# usb_serial.net
KiCad netlist of a schematic drawn in Altium Designer
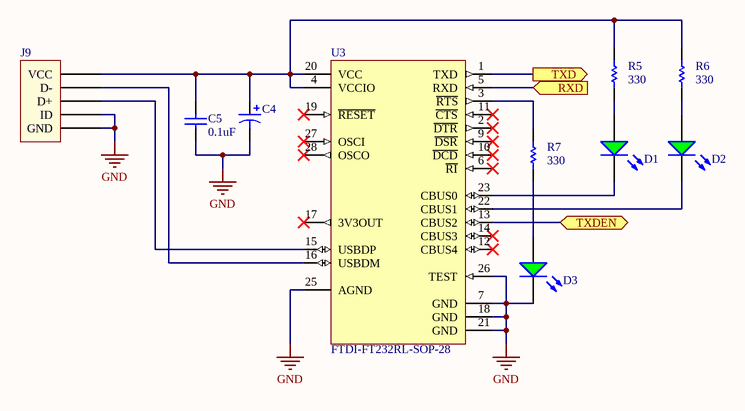
[diagram p0: usb_serial.SchDoc]

(export (version "E")
  (design (tool "Eeschema 10.0.6"))
  (components
    (comp (ref "C4")
      (value "Cap Pol2")
      (footprint "PCB-egxxoj2f8mz0uec15l92-1")
      (fields (field (name "MANUFACTURER PART NUMBER") "F981C105MMA"))
      (libsource (lib "CommunityVault") (part "CMP-7994653-3"))
    )
    (comp (ref "C5")
      (value "0.1uF")
      (footprint "CAPC1608X90X35NL20T15")
      (description "CAP CER 0.1UF 50V 10% X7R 0603")
      (libsource (lib "CommunityVault") (part "CMP-120344-2"))
    )
    (comp (ref "D1")
      (value "SYM-ec4c254b98bc338b-2")
      (footprint "PCB-9uwk2xd6chnjs8ehct7l-1")
      (description "Led; 0603 Smt Led, Green, Alingap, Water Clear Lens, 140 Deg Viewing Angle")
      (libsource (lib "CommunityVault") (part "CMP-ec4c254b98bc338b-4"))
    )
    (comp (ref "D2")
      (value "SYM-ec4c254b98bc338b-2")
      (footprint "PCB-9uwk2xd6chnjs8ehct7l-1")
      (description "Led; 0603 Smt Led, Green, Alingap, Water Clear Lens, 140 Deg Viewing Angle")
      (libsource (lib "CommunityVault") (part "CMP-ec4c254b98bc338b-4"))
    )
    (comp (ref "D3")
      (value "SYM-ec4c254b98bc338b-2")
      (footprint "PCB-9uwk2xd6chnjs8ehct7l-1")
      (description "Led; 0603 Smt Led, Green, Alingap, Water Clear Lens, 140 Deg Viewing Angle")
      (libsource (lib "CommunityVault") (part "CMP-ec4c254b98bc338b-4"))
    )
    (comp (ref "J9")
      (value "Samtec SPM-05-S-B-RA-PF")
      (footprint "PCB-zq8ywneimcsz1qyvw1ex-1")
      (description "Conn USB M 5 POS Solder RA Thru-Hole 5 Terminal 1 Port")
      (fields (field (name "MANUFACTURER PART NUMBER") "SPM-05-S-B-RA-PF"))
      (libsource (lib "CommunityVault") (part "CMP-d3c01be030ed0c07-2"))
    )
    (comp (ref "R5")
      (value "330")
      (footprint "PCB-1852941-1")
      (description "RESISTOR, RC21 0603 330R")
      (fields (field (name "MANUFACTURER PART NUMBER") "RC0603JR-07330RL"))
      (libsource (lib "CommunityVault") (part "CMP-1852941-3"))
    )
    (comp (ref "R6")
      (value "330")
      (footprint "PCB-1852941-1")
      (description "RESISTOR, RC21 0603 330R")
      (fields (field (name "MANUFACTURER PART NUMBER") "RC0603JR-07330RL"))
      (libsource (lib "CommunityVault") (part "CMP-1852941-3"))
    )
    (comp (ref "R7")
      (value "330")
      (footprint "PCB-1852941-1")
      (description "RESISTOR, RC21 0603 330R")
      (fields (field (name "MANUFACTURER PART NUMBER") "RC0603JR-07330RL"))
      (libsource (lib "CommunityVault") (part "CMP-1852941-3"))
    )
    (comp (ref "U3")
      (value "FTDI-FT232RL-SOP-28")
      (footprint "SOP65P780X200-28N")
      (description "SMD IC Interface; USB to UART; Speed 300b-3Mbaud; VCC 1.8V-5.25V")
      (fields (field (name "MANUFACTURER PART NUMBER") "FT232RL"))
      (libsource (lib "CommunityVault") (part "CMP-1159378-16"))
    )
  )
  (nets
    (net (code "1") (name "/RXD") (class "Default")
      (node (ref "U3") (pin "5") (pinfunction "RXD_5") (pintype "input"))
    )
    (net (code "2") (name "/TXD") (class "Default")
      (node (ref "U3") (pin "1") (pinfunction "TXD_1") (pintype "output"))
    )
    (net (code "3") (name "/TXDEN") (class "Default")
      (node (ref "U3") (pin "13") (pinfunction "CBUS2_13") (pintype "bidirectional"))
    )
    (net (code "4") (name "GND") (class "Default")
      (node (ref "C4") (pin "2") (pinfunction "2_2") (pintype "passive"))
      (node (ref "C5") (pin "1") (pinfunction "1_1") (pintype "passive"))
      (node (ref "D3") (pin "C") (pinfunction "C_C") (pintype "passive"))
      (node (ref "J9") (pin "4") (pinfunction "ID_4") (pintype "passive"))
      (node (ref "J9") (pin "5") (pinfunction "GND_5") (pintype "passive"))
      (node (ref "U3") (pin "18") (pinfunction "GND_18") (pintype "power_in"))
      (node (ref "U3") (pin "21") (pinfunction "GND_21") (pintype "power_in"))
      (node (ref "U3") (pin "25") (pinfunction "AGND_25") (pintype "power_in"))
      (node (ref "U3") (pin "26") (pinfunction "TEST_26") (pintype "input"))
      (node (ref "U3") (pin "7") (pinfunction "GND_7") (pintype "power_in"))
    )
    (net (code "5") (name "Net-(D1-PadA)") (class "Default")
      (node (ref "D1") (pin "A") (pinfunction "A_A") (pintype "passive"))
      (node (ref "R5") (pin "1") (pinfunction "1_1") (pintype "passive"))
    )
    (net (code "6") (name "Net-(D2-PadA)") (class "Default")
      (node (ref "D2") (pin "A") (pinfunction "A_A") (pintype "passive"))
      (node (ref "R6") (pin "1") (pinfunction "1_1") (pintype "passive"))
    )
    (net (code "7") (name "Net-(D3-PadA)") (class "Default")
      (node (ref "D3") (pin "A") (pinfunction "A_A") (pintype "passive"))
      (node (ref "R7") (pin "1") (pinfunction "1_1") (pintype "passive"))
    )
    (net (code "8") (name "Net-(J9-D+)") (class "Default")
      (node (ref "J9") (pin "3") (pinfunction "D+_3") (pintype "passive"))
      (node (ref "U3") (pin "15") (pinfunction "USBDP_15") (pintype "bidirectional"))
    )
    (net (code "9") (name "Net-(J9-D-)") (class "Default")
      (node (ref "J9") (pin "2") (pinfunction "D-_2") (pintype "passive"))
      (node (ref "U3") (pin "16") (pinfunction "USBDM_16") (pintype "bidirectional"))
    )
    (net (code "10") (name "Net-(J9-VCC)") (class "Default")
      (node (ref "C4") (pin "1") (pinfunction "1_1") (pintype "passive"))
      (node (ref "C5") (pin "2") (pinfunction "2_2") (pintype "passive"))
      (node (ref "J9") (pin "1") (pinfunction "VCC_1") (pintype "passive"))
      (node (ref "R5") (pin "2") (pinfunction "2_2") (pintype "passive"))
      (node (ref "R6") (pin "2") (pinfunction "2_2") (pintype "passive"))
      (node (ref "U3") (pin "20") (pinfunction "VCC_20") (pintype "power_in"))
      (node (ref "U3") (pin "4") (pinfunction "VCCIO_4") (pintype "power_in"))
    )
    (net (code "11") (name "Net-(U3-CBUS0)") (class "Default")
      (node (ref "D1") (pin "C") (pinfunction "C_C") (pintype "passive"))
      (node (ref "U3") (pin "23") (pinfunction "CBUS0_23") (pintype "bidirectional"))
    )
    (net (code "12") (name "Net-(U3-CBUS1)") (class "Default")
      (node (ref "D2") (pin "C") (pinfunction "C_C") (pintype "passive"))
      (node (ref "U3") (pin "22") (pinfunction "CBUS1_22") (pintype "bidirectional"))
    )
    (net (code "13") (name "Net-(U3-~{RTS})") (class "Default")
      (node (ref "R7") (pin "2") (pinfunction "2_2") (pintype "passive"))
      (node (ref "U3") (pin "3") (pinfunction "~{RTS}_3") (pintype "output"))
    )
    (net (code "14") (name "unconnected-(U3-3V3OUT-Pad17)") (class "Default")
      (node (ref "U3") (pin "17") (pinfunction "3V3OUT_17") (pintype "output+no_connect"))
    )
    (net (code "15") (name "unconnected-(U3-CBUS3-Pad14)") (class "Default")
      (node (ref "U3") (pin "14") (pinfunction "CBUS3_14") (pintype "bidirectional+no_connect"))
    )
    (net (code "16") (name "unconnected-(U3-CBUS4-Pad12)") (class "Default")
      (node (ref "U3") (pin "12") (pinfunction "CBUS4_12") (pintype "bidirectional+no_connect"))
    )
    (net (code "17") (name "unconnected-(U3-OSCI-Pad27)") (class "Default")
      (node (ref "U3") (pin "27") (pinfunction "OSCI_27") (pintype "input+no_connect"))
    )
    (net (code "18") (name "unconnected-(U3-OSCO-Pad28)") (class "Default")
      (node (ref "U3") (pin "28") (pinfunction "OSCO_28") (pintype "output+no_connect"))
    )
    (net (code "19") (name "unconnected-(U3-~{CTS}-Pad11)") (class "Default")
      (node (ref "U3") (pin "11") (pinfunction "~{CTS}_11") (pintype "input+no_connect"))
    )
    (net (code "20") (name "unconnected-(U3-~{DCD}-Pad10)") (class "Default")
      (node (ref "U3") (pin "10") (pinfunction "~{DCD}_10") (pintype "input+no_connect"))
    )
    (net (code "21") (name "unconnected-(U3-~{DSR}-Pad9)") (class "Default")
      (node (ref "U3") (pin "9") (pinfunction "~{DSR}_9") (pintype "input+no_connect"))
    )
    (net (code "22") (name "unconnected-(U3-~{DTR}-Pad2)") (class "Default")
      (node (ref "U3") (pin "2") (pinfunction "~{DTR}_2") (pintype "output+no_connect"))
    )
    (net (code "23") (name "unconnected-(U3-~{RESET}-Pad19)") (class "Default")
      (node (ref "U3") (pin "19") (pinfunction "~{RESET}_19") (pintype "input+no_connect"))
    )
    (net (code "24") (name "unconnected-(U3-~{RI}-Pad6)") (class "Default")
      (node (ref "U3") (pin "6") (pinfunction "~{RI}_6") (pintype "input+no_connect"))
    )
  )
)
